# power-input.net
KiCad netlist of a schematic drawn in Altium Designer
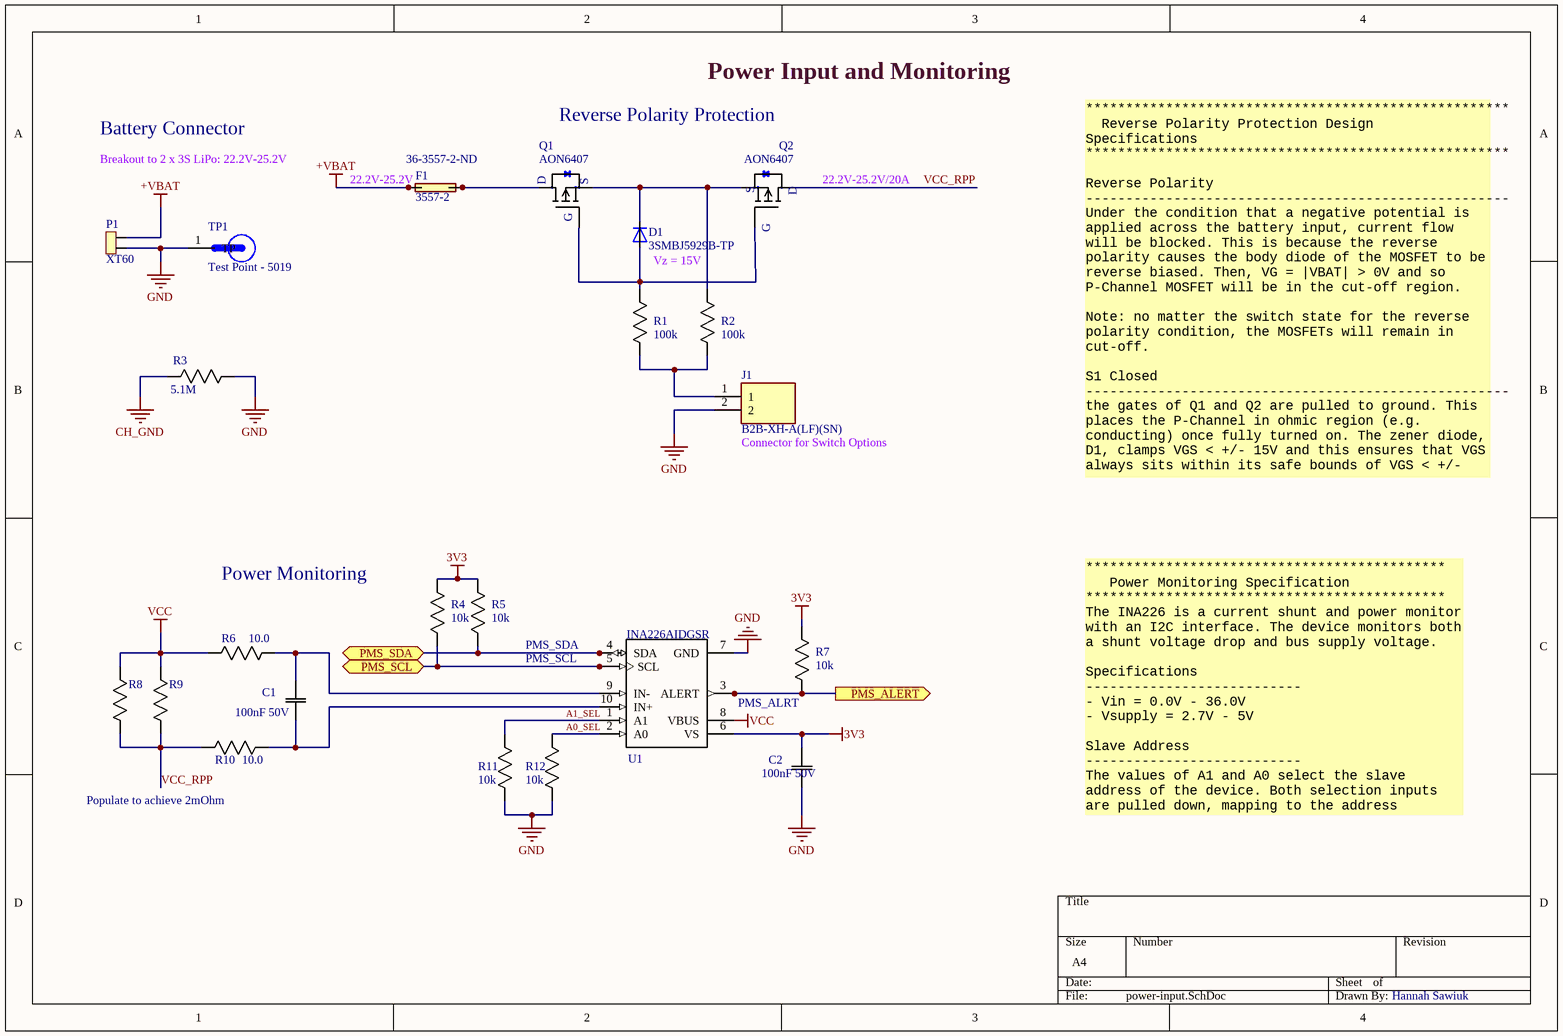
[diagram p0: power-input.SchDoc]

(export (version "E")
  (design (tool "Eeschema 10.0.6"))
  (components
    (comp (ref "C1")
      (value "100nF 50V")
      (footprint "0805")
      (description "CAP CER 0.1UF 50V X7R 0805")
      (fields (field (name "TOLERANCE") "10%"))
      (libsource (lib "AltiumLibraries") (part "CAP 100nF 50V"))
    )
    (comp (ref "C2")
      (value "100nF 50V")
      (footprint "0805")
      (description "CAP CER 0.1UF 50V X7R 0805")
      (fields (field (name "TOLERANCE") "10%"))
      (libsource (lib "AltiumLibraries") (part "CAP 100nF 50V"))
    )
    (comp (ref "D1")
      (value "3SMBJ5929B-TP")
      (footprint "SOD-123")
      (description "Diode ZENER 15V 3W")
      (libsource (lib "AltiumLibraries") (part "DIODE ZENER 15V 3W"))
    )
    (comp (ref "F1")
      (value "3557-2")
      (footprint "FUSE-3549-2")
      (description "Fuse Block 30A 500V 1 Circuit Blade Through Hole")
      (fields
        (field (name "MF") "Keystone Electronics")
        (field (name "SUPPLIER PART NUMBER 1") "36-3557-2-ND")
      )
      (libsource (lib "AltiumLibraries") (part "FUSE BLADE"))
    )
    (comp (ref "J1")
      (value "B2B-XH-A(LF)(SN)")
      (footprint "JST_B2B-XH-A(LF)(SN)")
      (description "Connector Header Through Hole 2 position 0.098 _2.50mm_\r\nJST XH")
      (fields (field (name "MP") "B2B-XH-A_LF__SN_") (field (name "MF") "JST Sales"))
      (libsource (lib "AltiumLibraries") (part "B2B-XH-A(LF)(SN)"))
    )
    (comp (ref "P1")
      (value "XT60")
      (footprint "Amass_XT60PW-M")
      (description "XT60 CONNECTORS FEMALE PAIR")
      (fields (field (name "MF") "SparkFun Electronics") (field (name "MP") "PRT-10474"))
      (libsource (lib "AltiumLibraries") (part "XT60 Connector"))
    )
    (comp (ref "PMS_ALRT")
      (value "Test Point (Via)")
      (footprint "TP")
      (libsource (lib "AltiumLibraries") (part "Test Point (Via)"))
    )
    (comp (ref "PMS_SCL")
      (value "Test Point (Via)")
      (footprint "TP")
      (libsource (lib "AltiumLibraries") (part "Test Point (Via)"))
    )
    (comp (ref "PMS_SDA")
      (value "Test Point (Via)")
      (footprint "TP")
      (libsource (lib "AltiumLibraries") (part "Test Point (Via)"))
    )
    (comp (ref "Q1")
      (value "AON6407")
      (footprint "8-PowerSMD")
      (description "MOSFET P-CH 30V 32A 8DFN")
      (fields (field (name "MF") "Alpha & Omega Semiconductor Inc."))
      (libsource (lib "AltiumLibraries") (part "MOSFET AON6407"))
    )
    (comp (ref "Q2")
      (value "AON6407")
      (footprint "8-PowerSMD")
      (description "MOSFET P-CH 30V 32A 8DFN")
      (fields (field (name "MF") "Alpha & Omega Semiconductor Inc."))
      (libsource (lib "AltiumLibraries") (part "MOSFET AON6407"))
    )
    (comp (ref "R1")
      (value "100k")
      (footprint "0805")
      (description "RES SMD 100K OHM 1% 1/8W 0805")
      (fields (field (name "TOLERANCE") "1%"))
      (libsource (lib "AltiumLibraries") (part "RES 100k 1/8W - 1%"))
    )
    (comp (ref "R2")
      (value "100k")
      (footprint "0805")
      (description "RES SMD 100K OHM 1% 1/8W 0805")
      (fields (field (name "TOLERANCE") "1%"))
      (libsource (lib "AltiumLibraries") (part "RES 100k 1/8W - 1%"))
    )
    (comp (ref "R3")
      (value "5.1M")
      (footprint "0805")
      (description "RES SMD 5.1 MOHM 5% 1/8W 0805")
      (fields (field (name "TOLERANCE") "5%"))
      (libsource (lib "AltiumLibraries") (part "RES 5.1M 1/8W-5%"))
    )
    (comp (ref "R4")
      (value "10k")
      (footprint "0805")
      (description "RES SMD 10K OHM 1% 1/8W 0805")
      (fields (field (name "TOLERANCE") "1%"))
      (libsource (lib "") (part "RES 10k 1/8W - 1%_1"))
    )
    (comp (ref "R5")
      (value "10k")
      (footprint "0805")
      (description "RES SMD 10K OHM 1% 1/8W 0805")
      (fields (field (name "TOLERANCE") "1%"))
      (libsource (lib "") (part "RES 10k 1/8W - 1%_1"))
    )
    (comp (ref "R6")
      (value "10.0")
      (footprint "0805")
      (description "RES SMD 10.0 OHM 1% 1/8W 0805")
      (fields (field (name "TOLERANCE") "1%"))
      (libsource (lib "AltiumLibraries") (part "RES 10.0 1/8W - 1%"))
    )
    (comp (ref "R7")
      (value "10k")
      (footprint "0805")
      (description "RES SMD 10K OHM 1% 1/8W 0805")
      (fields (field (name "TOLERANCE") "1%"))
      (libsource (lib "") (part "RES 10k 1/8W - 1%_1"))
    )
    (comp (ref "R8")
      (value "2mOHM")
      (footprint "2512")
      (description "RES SMD 2m OHM 1% 1W 1206")
      (fields (field (name "TOLERANCE") "1%"))
      (libsource (lib "AltiumLibraries") (part "RES 2m 1W"))
    )
    (comp (ref "R9")
      (value "2mOHM")
      (footprint "2512")
      (description "RES SMD 2m OHM 1% 1W 1206")
      (fields (field (name "TOLERANCE") "1%"))
      (libsource (lib "AltiumLibraries") (part "RES 2m 1W"))
    )
    (comp (ref "R10")
      (value "10.0")
      (footprint "0805")
      (description "RES SMD 10.0 OHM 1% 1/8W 0805")
      (fields (field (name "TOLERANCE") "1%"))
      (libsource (lib "AltiumLibraries") (part "RES 10.0 1/8W - 1%"))
    )
    (comp (ref "R11")
      (value "10k")
      (footprint "0805")
      (description "RES SMD 10K OHM 1% 1/8W 0805")
      (fields (field (name "TOLERANCE") "1%"))
      (libsource (lib "AltiumLibraries") (part "RES 10k 1/8W - 1%"))
    )
    (comp (ref "R12")
      (value "10k")
      (footprint "0805")
      (description "RES SMD 10K OHM 1% 1/8W 0805")
      (fields (field (name "TOLERANCE") "1%"))
      (libsource (lib "AltiumLibraries") (part "RES 10k 1/8W - 1%"))
    )
    (comp (ref "TP1")
      (value "Test Point - 5019")
      (footprint "TP380X203")
      (description "PC Test Point, Miniature Phosphor Bronze, Silver Plating Surface Mount Mounting Type")
      (fields (field (name "MP") "5019") (field (name "MF") "Keystone Electronics"))
      (libsource (lib "AltiumLibraries") (part "Test Point - 5019"))
    )
    (comp (ref "U1")
      (value "INA226AIDGSR")
      (footprint "10-VSSOP")
      (fields (field (name "MF") "Texas Instruments"))
      (libsource (lib "AltiumLibraries") (part "IC INA226AIDGSR"))
    )
  )
  (nets
    (net (code "1") (name "+VBAT") (class "Default")
      (node (ref "F1") (pin "3") (pinfunction "2A_3") (pintype "passive"))
      (node (ref "F1") (pin "4") (pinfunction "2B_4") (pintype "passive"))
      (node (ref "P1") (pin "2") (pinfunction "2_2") (pintype "passive"))
    )
    (net (code "2") (name "/A0_SEL") (class "Default")
      (node (ref "R12") (pin "1") (pinfunction "R1_1") (pintype "passive"))
      (node (ref "U1") (pin "2") (pinfunction "A0_2") (pintype "input"))
    )
    (net (code "3") (name "/A1_SEL") (class "Default")
      (node (ref "R11") (pin "1") (pinfunction "R1_1") (pintype "passive"))
      (node (ref "U1") (pin "1") (pinfunction "A1_1") (pintype "input"))
    )
    (net (code "4") (name "/PMS_ALERT") (class "Default")
      (node (ref "PMS_ALRT") (pin "1") (pinfunction "1_1") (pintype "passive"))
      (node (ref "R7") (pin "2") (pinfunction "R2_2") (pintype "passive"))
      (node (ref "U1") (pin "3") (pinfunction "ALERT_3") (pintype "output"))
    )
    (net (code "5") (name "/PMS_SCL") (class "Default")
      (node (ref "PMS_SCL") (pin "1") (pinfunction "1_1") (pintype "passive"))
      (node (ref "R4") (pin "2") (pinfunction "R2_2") (pintype "passive"))
      (node (ref "U1") (pin "5") (pinfunction "SCL_5") (pintype "input"))
    )
    (net (code "6") (name "/PMS_SDA") (class "Default")
      (node (ref "PMS_SDA") (pin "1") (pinfunction "1_1") (pintype "passive"))
      (node (ref "R5") (pin "2") (pinfunction "R2_2") (pintype "passive"))
      (node (ref "U1") (pin "4") (pinfunction "SDA_4") (pintype "bidirectional"))
    )
    (net (code "7") (name "/VCC_RPP") (class "Default")
      (node (ref "Q2") (pin "D") (pinfunction "D_D") (pintype "passive"))
      (node (ref "R10") (pin "2") (pinfunction "R2_2") (pintype "passive"))
      (node (ref "R8") (pin "2") (pinfunction "R2_2") (pintype "passive"))
      (node (ref "R9") (pin "2") (pinfunction "R2_2") (pintype "passive"))
    )
    (net (code "8") (name "3V3") (class "Default")
      (node (ref "C2") (pin "2") (pinfunction "C2_2") (pintype "passive"))
      (node (ref "R4") (pin "1") (pinfunction "R1_1") (pintype "passive"))
      (node (ref "R5") (pin "1") (pinfunction "R1_1") (pintype "passive"))
      (node (ref "R7") (pin "1") (pinfunction "R1_1") (pintype "passive"))
      (node (ref "U1") (pin "6") (pinfunction "VS_6") (pintype "power_in"))
    )
    (net (code "9") (name "CH_GND") (class "Default")
      (node (ref "R3") (pin "2") (pinfunction "R2_2") (pintype "passive"))
    )
    (net (code "10") (name "GND") (class "Default")
      (node (ref "C2") (pin "1") (pinfunction "C1_1") (pintype "passive"))
      (node (ref "J1") (pin "2") (pinfunction "2_2") (pintype "passive"))
      (node (ref "P1") (pin "1") (pinfunction "1_1") (pintype "passive"))
      (node (ref "R11") (pin "2") (pinfunction "R2_2") (pintype "passive"))
      (node (ref "R12") (pin "2") (pinfunction "R2_2") (pintype "passive"))
      (node (ref "R3") (pin "1") (pinfunction "R1_1") (pintype "passive"))
      (node (ref "TP1") (pin "1") (pinfunction "TP_1") (pintype "passive"))
      (node (ref "U1") (pin "7") (pinfunction "GND_7") (pintype "power_in"))
    )
    (net (code "11") (name "Net-(C1-C1)") (class "Default")
      (node (ref "C1") (pin "1") (pinfunction "C1_1") (pintype "passive"))
      (node (ref "R10") (pin "1") (pinfunction "R1_1") (pintype "passive"))
      (node (ref "U1") (pin "10") (pinfunction "IN+_10") (pintype "input"))
    )
    (net (code "12") (name "Net-(C1-C2)") (class "Default")
      (node (ref "C1") (pin "2") (pinfunction "C2_2") (pintype "passive"))
      (node (ref "R6") (pin "1") (pinfunction "R1_1") (pintype "passive"))
      (node (ref "U1") (pin "9") (pinfunction "IN-_9") (pintype "input"))
    )
    (net (code "13") (name "Net-(F1-1A)") (class "Default")
      (node (ref "F1") (pin "1") (pinfunction "1A_1") (pintype "passive"))
      (node (ref "F1") (pin "2") (pinfunction "1B_2") (pintype "passive"))
      (node (ref "Q1") (pin "D") (pinfunction "D_D") (pintype "passive"))
    )
    (net (code "14") (name "Net-(R1-R1)") (class "Default")
      (node (ref "D1") (pin "A") (pinfunction "A_A") (pintype "passive"))
      (node (ref "Q1") (pin "G") (pinfunction "G_G") (pintype "passive"))
      (node (ref "Q2") (pin "G") (pinfunction "G_G") (pintype "passive"))
      (node (ref "R1") (pin "1") (pinfunction "R1_1") (pintype "passive"))
    )
    (net (code "15") (name "Net-(R1-R2)") (class "Default")
      (node (ref "J1") (pin "1") (pinfunction "1_1") (pintype "passive"))
      (node (ref "R1") (pin "2") (pinfunction "R2_2") (pintype "passive"))
      (node (ref "R2") (pin "2") (pinfunction "R2_2") (pintype "passive"))
    )
    (net (code "16") (name "Net-(R2-R1)") (class "Default")
      (node (ref "D1") (pin "C") (pinfunction "C_C") (pintype "passive"))
      (node (ref "Q1") (pin "S") (pinfunction "S_S") (pintype "passive"))
      (node (ref "Q2") (pin "S") (pinfunction "S_S") (pintype "passive"))
      (node (ref "R2") (pin "1") (pinfunction "R1_1") (pintype "passive"))
    )
    (net (code "17") (name "VCC") (class "Default")
      (node (ref "R6") (pin "2") (pinfunction "R2_2") (pintype "passive"))
      (node (ref "R8") (pin "1") (pinfunction "R1_1") (pintype "passive"))
      (node (ref "R9") (pin "1") (pinfunction "R1_1") (pintype "passive"))
      (node (ref "U1") (pin "8") (pinfunction "VBUS_8") (pintype "power_in"))
    )
  )
)
